# GaggiaBoard_V2.net
KiCad netlist of a schematic drawn in EAGLE
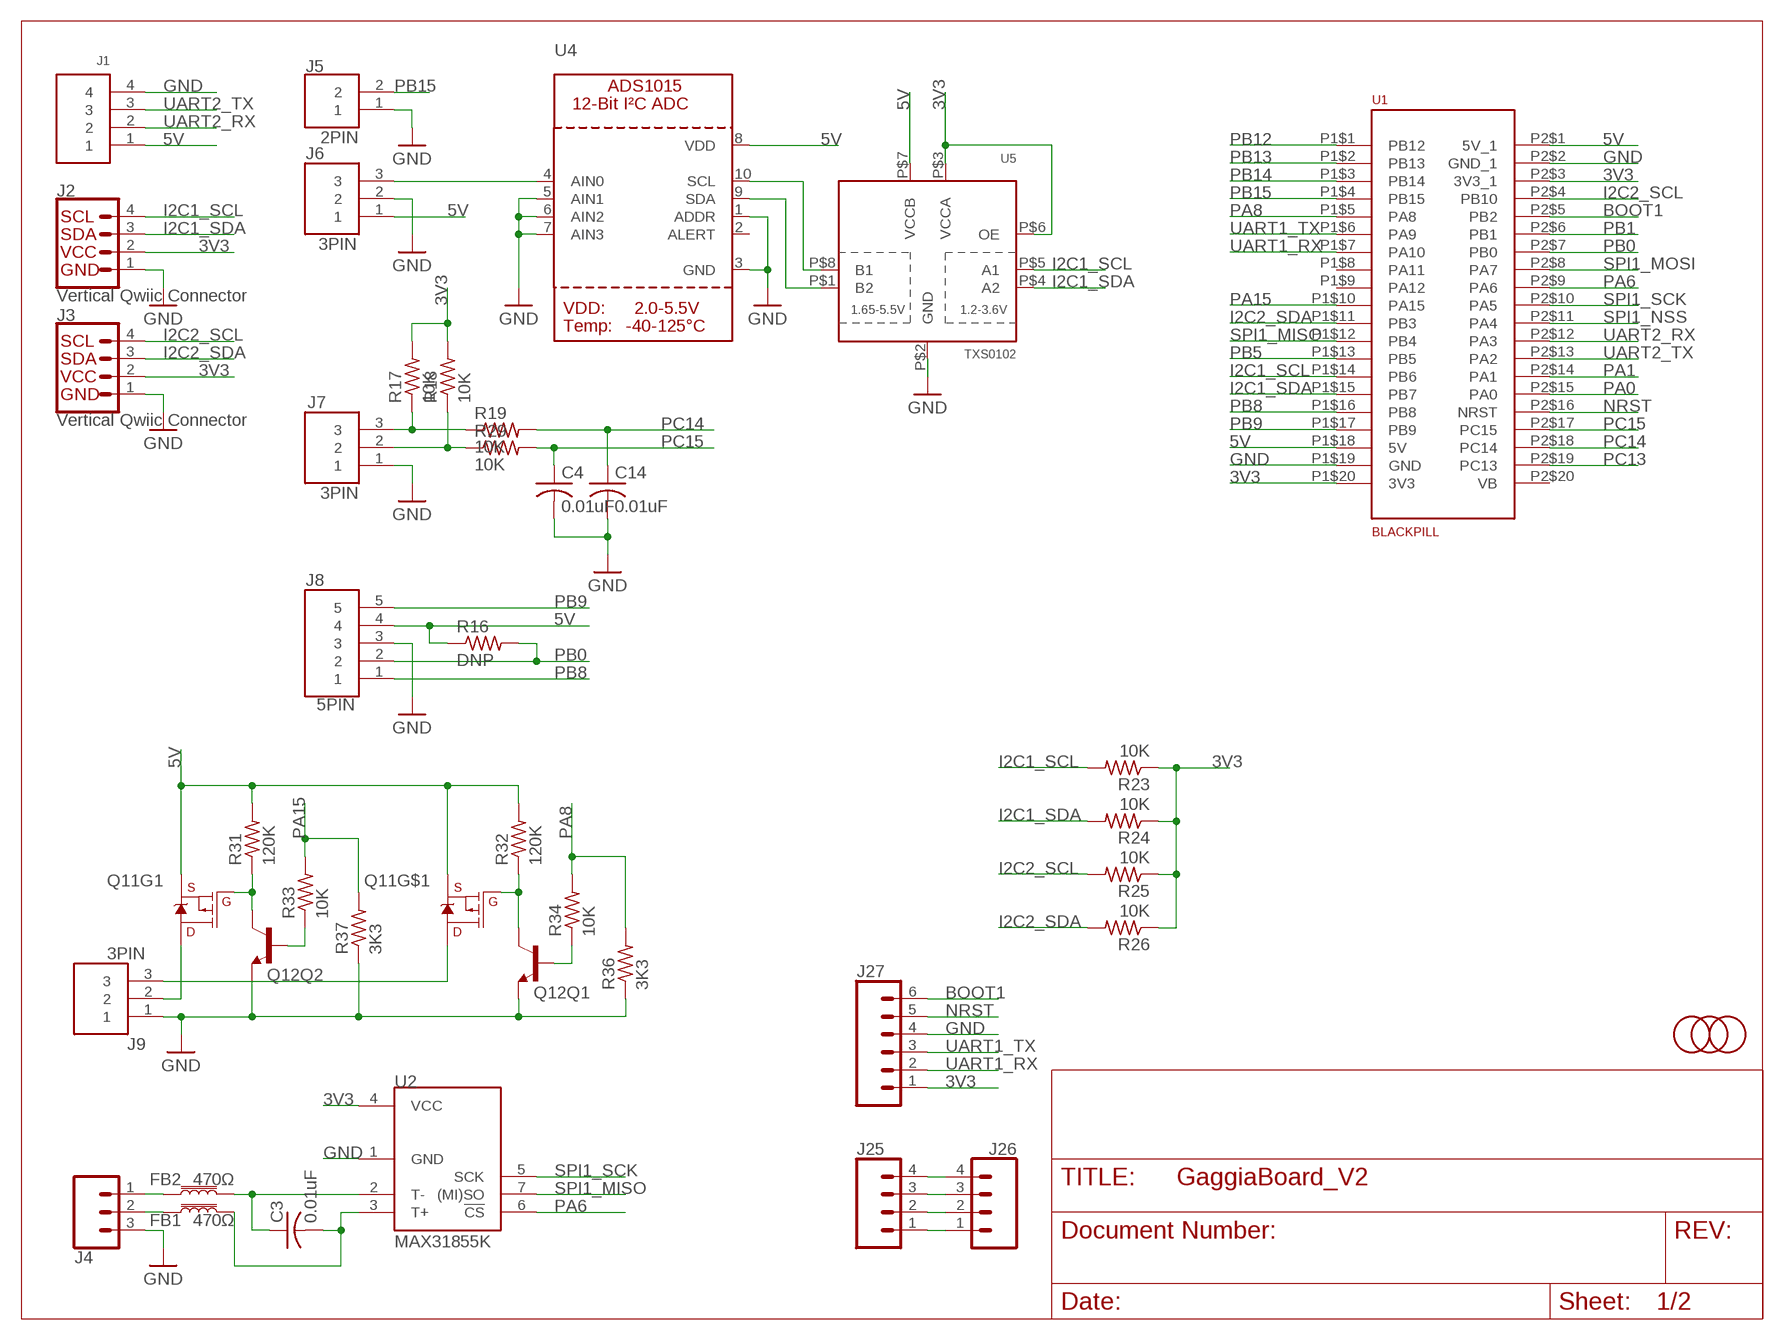
[diagram p0: schematic, sheet 1]
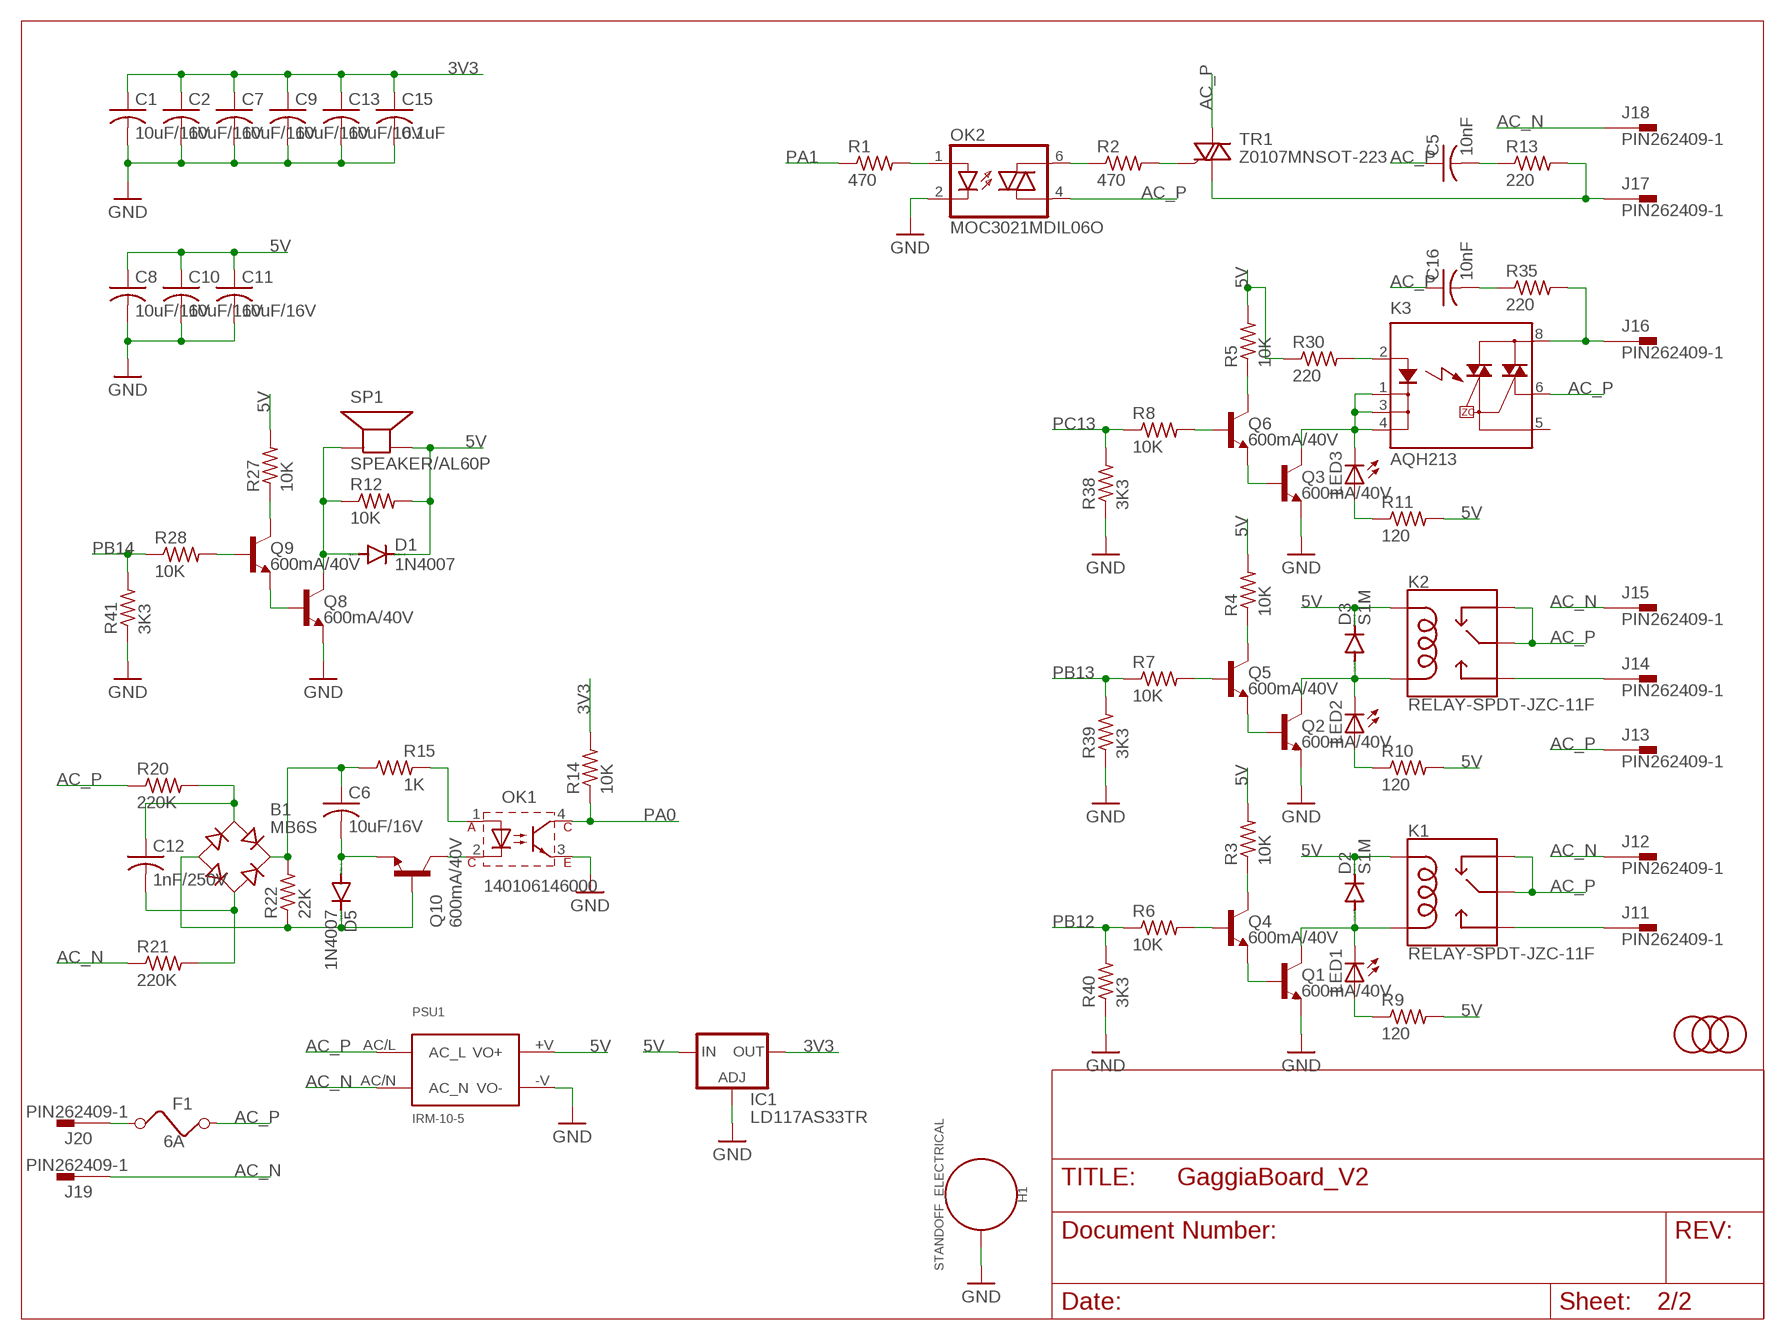
[diagram p1: schematic, sheet 2]

(export (version "E")
  (design (tool "Eeschema 10.0.6"))
  (components
    (comp (ref "C3")
      (value "0.01uF")
      (footprint "eagle-import:C0603")
      (libsource (lib "eagle-import") (part "C-USC0603"))
    )
    (comp (ref "C4")
      (value "0.01uF")
      (footprint "eagle-import:C0603")
      (libsource (lib "eagle-import") (part "C-USC0603"))
    )
    (comp (ref "C14")
      (value "0.01uF")
      (footprint "eagle-import:C0603")
      (libsource (lib "eagle-import") (part "C-USC0603"))
    )
    (comp (ref "FB1")
      (value "470Ω")
      (footprint "eagle-import:0603")
      (libsource (lib "eagle-import") (part "FERRITE_BEAD-0603-470Ω-100MHZ-1A-200MILIΩ"))
    )
    (comp (ref "FB2")
      (value "470Ω")
      (footprint "eagle-import:0603")
      (libsource (lib "eagle-import") (part "FERRITE_BEAD-0603-470Ω-100MHZ-1A-200MILIΩ"))
    )
    (comp (ref "J1")
      (value "4PIN")
      (footprint "eagle-import:B4B-XH-K-S")
      (libsource (lib "eagle-import") (part "4PIN"))
    )
    (comp (ref "J2")
      (value "Vertical Qwiic Connector")
      (footprint "eagle-import:JST04_1MM_VERT")
      (libsource (lib "eagle-import") (part "QWIIC_CONNECTOR"))
    )
    (comp (ref "J3")
      (value "Vertical Qwiic Connector")
      (footprint "eagle-import:JST04_1MM_VERT")
      (libsource (lib "eagle-import") (part "QWIIC_CONNECTOR"))
    )
    (comp (ref "J4")
      (value "CONN_03SCREW")
      (footprint "eagle-import:SCREWTERMINAL-3.5MM-3")
      (libsource (lib "eagle-import") (part "CONN_03SCREW"))
    )
    (comp (ref "J5")
      (value "2PIN")
      (footprint "eagle-import:B2B-PH-K-S")
      (libsource (lib "eagle-import") (part "2PIN"))
    )
    (comp (ref "J6")
      (value "3PIN")
      (footprint "eagle-import:B3B-PH-K-S")
      (libsource (lib "eagle-import") (part "3PIN"))
    )
    (comp (ref "J7")
      (value "3PIN")
      (footprint "eagle-import:B3B-PH-K-S")
      (libsource (lib "eagle-import") (part "3PIN"))
    )
    (comp (ref "J8")
      (value "5PIN")
      (footprint "eagle-import:B5B-PH-K-S")
      (libsource (lib "eagle-import") (part "5PIN"))
    )
    (comp (ref "J9")
      (value "3PIN")
      (footprint "eagle-import:B3B-PH-K-S")
      (libsource (lib "eagle-import") (part "3PIN"))
    )
    (comp (ref "J25")
      (value "CONN_041X04_NO_SILK")
      (footprint "eagle-import:1X04_NO_SILK")
      (libsource (lib "eagle-import") (part "CONN_041X04_NO_SILK"))
    )
    (comp (ref "J26")
      (value "CONN_041X04_NO_SILK")
      (footprint "eagle-import:1X04_NO_SILK")
      (libsource (lib "eagle-import") (part "CONN_041X04_NO_SILK"))
    )
    (comp (ref "J27")
      (value "CONN_06NO_SILK_FEMALE_PTH")
      (footprint "eagle-import:1X06_NO_SILK")
      (libsource (lib "eagle-import") (part "CONN_06NO_SILK_FEMALE_PTH"))
    )
    (comp (ref "MARK1")
      (value "FIDUCIAL")
      (footprint "eagle-import:FIDUCIAL_1MM")
      (libsource (lib "eagle-import") (part "FIDUCIAL"))
    )
    (comp (ref "MARK2")
      (value "FIDUCIAL")
      (footprint "eagle-import:FIDUCIAL_1MM")
      (libsource (lib "eagle-import") (part "FIDUCIAL"))
    )
    (comp (ref "MARK5")
      (value "FIDUCIAL")
      (footprint "eagle-import:FIDUCIAL_1MM")
      (libsource (lib "eagle-import") (part "FIDUCIAL"))
    )
    (comp (ref "Q11")
      (value "MOSFET_PCH_DUAL-DMP2240UDM")
      (footprint "eagle-import:SOT26")
      (fields (field (name "LCSC") "C397948"))
      (libsource (lib "eagle-import") (part "MOSFET_PCH_DUAL-DMP2240UDM"))
    )
    (comp (ref "Q12")
      (value "TRANS_NPN_DUAL-MBT3904DW1T1")
      (footprint "eagle-import:SC70-6")
      (fields (field (name "LCSC") "C896759"))
      (libsource (lib "eagle-import") (part "TRANS_NPN_DUAL-MBT3904DW1T1"))
    )
    (comp (ref "R16")
      (value "DNP")
      (footprint "eagle-import:R0603")
      (libsource (lib "eagle-import") (part "R-US_R0603"))
    )
    (comp (ref "R17")
      (value "10K")
      (footprint "eagle-import:R0603")
      (libsource (lib "eagle-import") (part "R-US_R0603"))
    )
    (comp (ref "R18")
      (value "10K")
      (footprint "eagle-import:R0603")
      (libsource (lib "eagle-import") (part "R-US_R0603"))
    )
    (comp (ref "R19")
      (value "10K")
      (footprint "eagle-import:R0603")
      (libsource (lib "eagle-import") (part "R-US_R0603"))
    )
    (comp (ref "R23")
      (value "10K")
      (footprint "eagle-import:R0603")
      (libsource (lib "eagle-import") (part "R-US_R0603"))
    )
    (comp (ref "R24")
      (value "10K")
      (footprint "eagle-import:R0603")
      (libsource (lib "eagle-import") (part "R-US_R0603"))
    )
    (comp (ref "R25")
      (value "10K")
      (footprint "eagle-import:R0603")
      (libsource (lib "eagle-import") (part "R-US_R0603"))
    )
    (comp (ref "R26")
      (value "10K")
      (footprint "eagle-import:R0603")
      (libsource (lib "eagle-import") (part "R-US_R0603"))
    )
    (comp (ref "R29")
      (value "10K")
      (footprint "eagle-import:R0603")
      (libsource (lib "eagle-import") (part "R-US_R0603"))
    )
    (comp (ref "R31")
      (value "120K")
      (footprint "eagle-import:R0603")
      (libsource (lib "eagle-import") (part "R-US_R0603"))
    )
    (comp (ref "R32")
      (value "120K")
      (footprint "eagle-import:R0603")
      (libsource (lib "eagle-import") (part "R-US_R0603"))
    )
    (comp (ref "R33")
      (value "10K")
      (footprint "eagle-import:R0603")
      (libsource (lib "eagle-import") (part "R-US_R0603"))
    )
    (comp (ref "R34")
      (value "10K")
      (footprint "eagle-import:R0603")
      (libsource (lib "eagle-import") (part "R-US_R0603"))
    )
    (comp (ref "R36")
      (value "3K3")
      (footprint "eagle-import:R0603")
      (libsource (lib "eagle-import") (part "R-US_R0603"))
    )
    (comp (ref "R37")
      (value "3K3")
      (footprint "eagle-import:R0603")
      (libsource (lib "eagle-import") (part "R-US_R0603"))
    )
    (comp (ref "U1")
      (value "BLACKPILL")
      (footprint "eagle-import:BLACKPILL")
      (libsource (lib "eagle-import") (part "BLACKPILL"))
    )
    (comp (ref "U2")
      (value "MAX31855K")
      (footprint "eagle-import:SO08")
      (libsource (lib "eagle-import") (part "MAX31855K"))
    )
    (comp (ref "U4")
      (value "ADC_ADS1015")
      (footprint "eagle-import:MSOP10")
      (libsource (lib "eagle-import") (part "ADC_ADS1015"))
    )
    (comp (ref "U5")
      (value "TXS0102")
      (footprint "eagle-import:VFSOP-8")
      (libsource (lib "eagle-import") (part "TXS0102"))
    )
    (comp (ref "B1")
      (value "MB6S")
      (footprint "eagle-import:SOIC-4")
      (libsource (lib "eagle-import") (part "MBS6"))
    )
    (comp (ref "C1")
      (value "10uF/16V")
      (footprint "eagle-import:C0603")
      (libsource (lib "eagle-import") (part "C-USC0603"))
    )
    (comp (ref "C2")
      (value "10uF/16V")
      (footprint "eagle-import:C0603")
      (libsource (lib "eagle-import") (part "C-USC0603"))
    )
    (comp (ref "C5")
      (value "10nF")
      (footprint "eagle-import:C1206")
      (libsource (lib "eagle-import") (part "C-USC1206"))
    )
    (comp (ref "C6")
      (value "10uF/16V")
      (footprint "eagle-import:C0603")
      (libsource (lib "eagle-import") (part "C-USC0603"))
    )
    (comp (ref "C7")
      (value "10uF/16V")
      (footprint "eagle-import:C0603")
      (libsource (lib "eagle-import") (part "C-USC0603"))
    )
    (comp (ref "C8")
      (value "10uF/16V")
      (footprint "eagle-import:C0603")
      (libsource (lib "eagle-import") (part "C-USC0603"))
    )
    (comp (ref "C9")
      (value "10uF/16V")
      (footprint "eagle-import:C0603")
      (libsource (lib "eagle-import") (part "C-USC0603"))
    )
    (comp (ref "C10")
      (value "10uF/16V")
      (footprint "eagle-import:C0603")
      (libsource (lib "eagle-import") (part "C-USC0603"))
    )
    (comp (ref "C11")
      (value "10uF/16V")
      (footprint "eagle-import:C0603")
      (libsource (lib "eagle-import") (part "C-USC0603"))
    )
    (comp (ref "C12")
      (value "1nF/250V")
      (footprint "eagle-import:C0603")
      (libsource (lib "eagle-import") (part "C-USC0603"))
    )
    (comp (ref "C13")
      (value "10uF/16V")
      (footprint "eagle-import:C0603")
      (libsource (lib "eagle-import") (part "C-USC0603"))
    )
    (comp (ref "C15")
      (value "0.1uF")
      (footprint "eagle-import:C0603")
      (libsource (lib "eagle-import") (part "C-USC0603"))
    )
    (comp (ref "C16")
      (value "10nF")
      (footprint "eagle-import:C1206")
      (libsource (lib "eagle-import") (part "C-USC1206"))
    )
    (comp (ref "D1")
      (value "1N4007")
      (footprint "eagle-import:DO214AC")
      (libsource (lib "eagle-import") (part "DIODE-DO214AC"))
    )
    (comp (ref "D2")
      (value "S1M")
      (footprint "eagle-import:SMA")
      (libsource (lib "eagle-import") (part "S1M"))
    )
    (comp (ref "D3")
      (value "S1M")
      (footprint "eagle-import:SMA")
      (libsource (lib "eagle-import") (part "S1M"))
    )
    (comp (ref "D5")
      (value "1N4007")
      (footprint "eagle-import:DO214AC")
      (libsource (lib "eagle-import") (part "DIODE-DO214AC"))
    )
    (comp (ref "F1")
      (value "6A")
      (footprint "eagle-import:FUSE")
      (libsource (lib "eagle-import") (part "FUSE"))
    )
    (comp (ref "H1")
      (value "STANDOFF_ELECTRICAL")
      (footprint "eagle-import:STANDOFF-ELECTRICAL")
      (libsource (lib "eagle-import") (part "STANDOFF_ELECTRICAL"))
    )
    (comp (ref "IC1")
      (value "LD117AS33TR")
      (footprint "eagle-import:SOT223")
      (libsource (lib "eagle-import") (part "LD117A?S33TR"))
    )
    (comp (ref "J11")
      (value "PIN262409-1")
      (footprint "eagle-import:62409-1")
      (libsource (lib "eagle-import") (part "PIN262409-1"))
    )
    (comp (ref "J12")
      (value "PIN262409-1")
      (footprint "eagle-import:62409-1")
      (libsource (lib "eagle-import") (part "PIN262409-1"))
    )
    (comp (ref "J13")
      (value "PIN262409-1")
      (footprint "eagle-import:62409-1")
      (libsource (lib "eagle-import") (part "PIN262409-1"))
    )
    (comp (ref "J14")
      (value "PIN262409-1")
      (footprint "eagle-import:62409-1")
      (libsource (lib "eagle-import") (part "PIN262409-1"))
    )
    (comp (ref "J15")
      (value "PIN262409-1")
      (footprint "eagle-import:62409-1")
      (libsource (lib "eagle-import") (part "PIN262409-1"))
    )
    (comp (ref "J16")
      (value "PIN262409-1")
      (footprint "eagle-import:62409-1")
      (libsource (lib "eagle-import") (part "PIN262409-1"))
    )
    (comp (ref "J17")
      (value "PIN262409-1")
      (footprint "eagle-import:62409-1")
      (libsource (lib "eagle-import") (part "PIN262409-1"))
    )
    (comp (ref "J18")
      (value "PIN262409-1")
      (footprint "eagle-import:62409-1")
      (libsource (lib "eagle-import") (part "PIN262409-1"))
    )
    (comp (ref "J19")
      (value "PIN262409-1")
      (footprint "eagle-import:62409-1")
      (libsource (lib "eagle-import") (part "PIN262409-1"))
    )
    (comp (ref "J20")
      (value "PIN262409-1")
      (footprint "eagle-import:62409-1")
      (libsource (lib "eagle-import") (part "PIN262409-1"))
    )
    (comp (ref "K1")
      (value "RELAY-SPDT-JZC-11F")
      (footprint "eagle-import:RELAY-JZC")
      (libsource (lib "eagle-import") (part "RELAY-SPDT-JZC-11F"))
    )
    (comp (ref "K2")
      (value "RELAY-SPDT-JZC-11F")
      (footprint "eagle-import:RELAY-JZC")
      (libsource (lib "eagle-import") (part "RELAY-SPDT-JZC-11F"))
    )
    (comp (ref "K3")
      (value "AQH213")
      (footprint "eagle-import:DIL07")
      (libsource (lib "eagle-import") (part "AQH213"))
    )
    (comp (ref "LED1")
      (value "LEDCHIPLED_1206")
      (footprint "eagle-import:CHIPLED_1206")
      (libsource (lib "eagle-import") (part "LEDCHIPLED_1206"))
    )
    (comp (ref "LED2")
      (value "LEDCHIPLED_1206")
      (footprint "eagle-import:CHIPLED_1206")
      (libsource (lib "eagle-import") (part "LEDCHIPLED_1206"))
    )
    (comp (ref "LED3")
      (value "LEDCHIPLED_1206")
      (footprint "eagle-import:CHIPLED_1206")
      (libsource (lib "eagle-import") (part "LEDCHIPLED_1206"))
    )
    (comp (ref "MARK3")
      (value "FIDUCIAL")
      (footprint "eagle-import:FIDUCIAL_1MM")
      (libsource (lib "eagle-import") (part "FIDUCIAL"))
    )
    (comp (ref "MARK4")
      (value "FIDUCIAL")
      (footprint "eagle-import:FIDUCIAL_1MM")
      (libsource (lib "eagle-import") (part "FIDUCIAL"))
    )
    (comp (ref "MARK6")
      (value "FIDUCIAL")
      (footprint "eagle-import:FIDUCIAL_1MM")
      (libsource (lib "eagle-import") (part "FIDUCIAL"))
    )
    (comp (ref "OK1")
      (value "140106146000")
      (footprint "eagle-import:WL-OCPT_LSOP4")
      (libsource (lib "eagle-import") (part "WL-OCPT_SERIES_101X_140106146000"))
    )
    (comp (ref "OK2")
      (value "MOC3021MDIL06O")
      (footprint "eagle-import:DIL06O")
      (libsource (lib "eagle-import") (part "MOC3021MDIL06O"))
    )
    (comp (ref "PSU1")
      (value "IRM-10-5")
      (footprint "eagle-import:IRM-10")
      (fields (field (name "SPICEPREFIX") "E"))
      (libsource (lib "eagle-import") (part "IRM-10-5"))
    )
    (comp (ref "Q1")
      (value "600mA/40V")
      (footprint "eagle-import:SOT23-3")
      (libsource (lib "eagle-import") (part "TRANS_NPN-MMBT2222AL"))
    )
    (comp (ref "Q2")
      (value "600mA/40V")
      (footprint "eagle-import:SOT23-3")
      (libsource (lib "eagle-import") (part "TRANS_NPN-MMBT2222AL"))
    )
    (comp (ref "Q3")
      (value "600mA/40V")
      (footprint "eagle-import:SOT23-3")
      (libsource (lib "eagle-import") (part "TRANS_NPN-MMBT2222AL"))
    )
    (comp (ref "Q4")
      (value "600mA/40V")
      (footprint "eagle-import:SOT23-3")
      (libsource (lib "eagle-import") (part "TRANS_NPN-MMBT2222AL"))
    )
    (comp (ref "Q5")
      (value "600mA/40V")
      (footprint "eagle-import:SOT23-3")
      (libsource (lib "eagle-import") (part "TRANS_NPN-MMBT2222AL"))
    )
    (comp (ref "Q6")
      (value "600mA/40V")
      (footprint "eagle-import:SOT23-3")
      (libsource (lib "eagle-import") (part "TRANS_NPN-MMBT2222AL"))
    )
    (comp (ref "Q8")
      (value "600mA/40V")
      (footprint "eagle-import:SOT23-3")
      (libsource (lib "eagle-import") (part "TRANS_NPN-MMBT2222AL"))
    )
    (comp (ref "Q9")
      (value "600mA/40V")
      (footprint "eagle-import:SOT23-3")
      (libsource (lib "eagle-import") (part "TRANS_NPN-MMBT2222AL"))
    )
    (comp (ref "Q10")
      (value "600mA/40V")
      (footprint "eagle-import:SOT23-3")
      (libsource (lib "eagle-import") (part "TRANS_NPN-MMBT2222AL"))
    )
    (comp (ref "R1")
      (value "470")
      (footprint "eagle-import:R0603")
      (libsource (lib "eagle-import") (part "R-US_R0603"))
    )
    (comp (ref "R2")
      (value "470")
      (footprint "eagle-import:R0603")
      (libsource (lib "eagle-import") (part "R-US_R0603"))
    )
    (comp (ref "R3")
      (value "10K")
      (footprint "eagle-import:R0603")
      (libsource (lib "eagle-import") (part "R-US_R0603"))
    )
    (comp (ref "R4")
      (value "10K")
      (footprint "eagle-import:R0603")
      (libsource (lib "eagle-import") (part "R-US_R0603"))
    )
    (comp (ref "R5")
      (value "10K")
      (footprint "eagle-import:R0603")
      (libsource (lib "eagle-import") (part "R-US_R0603"))
    )
    (comp (ref "R6")
      (value "10K")
      (footprint "eagle-import:R0603")
      (libsource (lib "eagle-import") (part "R-US_R0603"))
    )
    (comp (ref "R7")
      (value "10K")
      (footprint "eagle-import:R0603")
      (libsource (lib "eagle-import") (part "R-US_R0603"))
    )
    (comp (ref "R8")
      (value "10K")
      (footprint "eagle-import:R0603")
      (libsource (lib "eagle-import") (part "R-US_R0603"))
    )
    (comp (ref "R9")
      (value "120")
      (footprint "eagle-import:R0603")
      (libsource (lib "eagle-import") (part "R-US_R0603"))
    )
    (comp (ref "R10")
      (value "120")
      (footprint "eagle-import:R0603")
      (libsource (lib "eagle-import") (part "R-US_R0603"))
    )
    (comp (ref "R11")
      (value "120")
      (footprint "eagle-import:R0603")
      (libsource (lib "eagle-import") (part "R-US_R0603"))
    )
    (comp (ref "R12")
      (value "10K")
      (footprint "eagle-import:R0603")
      (libsource (lib "eagle-import") (part "R-US_R0603"))
    )
    (comp (ref "R13")
      (value "220")
      (footprint "eagle-import:R2512")
      (libsource (lib "eagle-import") (part "R-US_R2512"))
    )
    (comp (ref "R14")
      (value "10K")
      (footprint "eagle-import:R0603")
      (libsource (lib "eagle-import") (part "R-US_R0603"))
    )
    (comp (ref "R15")
      (value "1K")
      (footprint "eagle-import:R0603")
      (libsource (lib "eagle-import") (part "R-US_R0603"))
    )
    (comp (ref "R20")
      (value "220K")
      (footprint "eagle-import:R1206")
      (libsource (lib "eagle-import") (part "R-US_R1206"))
    )
    (comp (ref "R21")
      (value "220K")
      (footprint "eagle-import:R1206")
      (libsource (lib "eagle-import") (part "R-US_R1206"))
    )
    (comp (ref "R22")
      (value "22K")
      (footprint "eagle-import:R0603")
      (libsource (lib "eagle-import") (part "R-US_R0603"))
    )
    (comp (ref "R27")
      (value "10K")
      (footprint "eagle-import:R0603")
      (libsource (lib "eagle-import") (part "R-US_R0603"))
    )
    (comp (ref "R28")
      (value "10K")
      (footprint "eagle-import:R0603")
      (libsource (lib "eagle-import") (part "R-US_R0603"))
    )
    (comp (ref "R30")
      (value "220")
      (footprint "eagle-import:R0603")
      (libsource (lib "eagle-import") (part "R-US_R0603"))
    )
    (comp (ref "R35")
      (value "220")
      (footprint "eagle-import:R2512")
      (libsource (lib "eagle-import") (part "R-US_R2512"))
    )
    (comp (ref "R38")
      (value "3K3")
      (footprint "eagle-import:R0603")
      (libsource (lib "eagle-import") (part "R-US_R0603"))
    )
    (comp (ref "R39")
      (value "3K3")
      (footprint "eagle-import:R0603")
      (libsource (lib "eagle-import") (part "R-US_R0603"))
    )
    (comp (ref "R40")
      (value "3K3")
      (footprint "eagle-import:R0603")
      (libsource (lib "eagle-import") (part "R-US_R0603"))
    )
    (comp (ref "R41")
      (value "3K3")
      (footprint "eagle-import:R0603")
      (libsource (lib "eagle-import") (part "R-US_R0603"))
    )
    (comp (ref "SP1")
      (value "SPEAKER/AL60P")
      (footprint "eagle-import:AL60P")
      (libsource (lib "eagle-import") (part "SPEAKER/AL60P"))
    )
    (comp (ref "TR1")
      (value "Z0107MNSOT-223")
      (footprint "eagle-import:SOT223")
      (libsource (lib "eagle-import") (part "Z0107MNSOT-223"))
    )
  )
  (nets
    (net (code "1") (name "3V3") (class "Default")
      (node (ref "C1") (pin "1") (pinfunction "1_1") (pintype "passive"))
      (node (ref "C13") (pin "1") (pinfunction "1_1") (pintype "passive"))
      (node (ref "C15") (pin "1") (pinfunction "1_1") (pintype "passive"))
      (node (ref "C2") (pin "1") (pinfunction "1_1") (pintype "passive"))
      (node (ref "C7") (pin "1") (pinfunction "1_1") (pintype "passive"))
      (node (ref "C9") (pin "1") (pinfunction "1_1") (pintype "passive"))
      (node (ref "IC1") (pin "4") (pinfunction "OUT_4") (pintype "passive"))
      (node (ref "J2") (pin "2") (pinfunction "2_2") (pintype "power_in"))
      (node (ref "J25") (pin "1") (pinfunction "1_1") (pintype "passive"))
      (node (ref "J26") (pin "1") (pinfunction "1_1") (pintype "passive"))
      (node (ref "J27") (pin "1") (pinfunction "1_1") (pintype "passive"))
      (node (ref "J3") (pin "2") (pinfunction "2_2") (pintype "power_in"))
      (node (ref "R14") (pin "2") (pinfunction "2_2") (pintype "passive"))
      (node (ref "R17") (pin "2") (pinfunction "2_2") (pintype "passive"))
      (node (ref "R18") (pin "2") (pinfunction "2_2") (pintype "passive"))
      (node (ref "R23") (pin "1") (pinfunction "1_1") (pintype "passive"))
      (node (ref "R24") (pin "1") (pinfunction "1_1") (pintype "passive"))
      (node (ref "R25") (pin "1") (pinfunction "1_1") (pintype "passive"))
      (node (ref "R26") (pin "1") (pinfunction "1_1") (pintype "passive"))
      (node (ref "U1") (pin "P1$20") (pinfunction "3V3_P1$20") (pintype "power_in"))
      (node (ref "U1") (pin "P2$3") (pinfunction "3V3_1_P2$3") (pintype "power_in"))
      (node (ref "U2") (pin "4") (pinfunction "VCC_4") (pintype "bidirectional"))
      (node (ref "U5") (pin "P$3") (pinfunction "VCCA_P$3") (pintype "bidirectional"))
      (node (ref "U5") (pin "P$6") (pinfunction "OE_P$6") (pintype "bidirectional"))
    )
    (net (code "2") (name "5V") (class "Default")
      (node (ref "C10") (pin "1") (pinfunction "1_1") (pintype "passive"))
      (node (ref "C11") (pin "1") (pinfunction "1_1") (pintype "passive"))
      (node (ref "C8") (pin "1") (pinfunction "1_1") (pintype "passive"))
      (node (ref "D1") (pin "C") (pinfunction "C_C") (pintype "passive"))
      (node (ref "D2") (pin "C") (pinfunction "C_C") (pintype "passive"))
      (node (ref "D3") (pin "C") (pinfunction "C_C") (pintype "passive"))
      (node (ref "IC1") (pin "3") (pinfunction "IN_3") (pintype "input"))
      (node (ref "J1") (pin "1") (pinfunction "1_1") (pintype "bidirectional"))
      (node (ref "J6") (pin "1") (pinfunction "1_1") (pintype "bidirectional"))
      (node (ref "J8") (pin "4") (pinfunction "4_4") (pintype "bidirectional"))
      (node (ref "K1") (pin "5") (pinfunction "COIL1_5") (pintype "bidirectional"))
      (node (ref "K2") (pin "5") (pinfunction "COIL1_5") (pintype "bidirectional"))
      (node (ref "PSU1") (pin "+V") (pinfunction "VO+_+V") (pintype "bidirectional"))
      (node (ref "Q11") (pin "S1") (pinfunction "S_S1") (pintype "bidirectional"))
      (node (ref "Q11") (pin "S2") (pinfunction "S_S2") (pintype "bidirectional"))
      (node (ref "R10") (pin "2") (pinfunction "2_2") (pintype "passive"))
      (node (ref "R11") (pin "2") (pinfunction "2_2") (pintype "passive"))
      (node (ref "R12") (pin "2") (pinfunction "2_2") (pintype "passive"))
      (node (ref "R16") (pin "1") (pinfunction "1_1") (pintype "passive"))
      (node (ref "R27") (pin "2") (pinfunction "2_2") (pintype "passive"))
      (node (ref "R3") (pin "2") (pinfunction "2_2") (pintype "passive"))
      (node (ref "R30") (pin "1") (pinfunction "1_1") (pintype "passive"))
      (node (ref "R31") (pin "2") (pinfunction "2_2") (pintype "passive"))
      (node (ref "R32") (pin "2") (pinfunction "2_2") (pintype "passive"))
      (node (ref "R4") (pin "2") (pinfunction "2_2") (pintype "passive"))
      (node (ref "R5") (pin "2") (pinfunction "2_2") (pintype "passive"))
      (node (ref "R9") (pin "2") (pinfunction "2_2") (pintype "passive"))
      (node (ref "SP1") (pin "2") (pinfunction "-_2") (pintype "passive"))
      (node (ref "U1") (pin "P1$18") (pinfunction "5V_P1$18") (pintype "power_in"))
      (node (ref "U1") (pin "P2$1") (pinfunction "5V_1_P2$1") (pintype "power_in"))
      (node (ref "U4") (pin "8") (pinfunction "VDD_8") (pintype "bidirectional"))
      (node (ref "U5") (pin "P$7") (pinfunction "VCCB_P$7") (pintype "bidirectional"))
    )
    (net (code "3") (name "AC_N") (class "Default")
      (node (ref "J12") (pin "A1") (pinfunction "1_A1") (pintype "passive"))
      (node (ref "J12") (pin "A2") (pinfunction "1_A2") (pintype "passive"))
      (node (ref "J15") (pin "A1") (pinfunction "1_A1") (pintype "passive"))
      (node (ref "J15") (pin "A2") (pinfunction "1_A2") (pintype "passive"))
      (node (ref "J18") (pin "A1") (pinfunction "1_A1") (pintype "passive"))
      (node (ref "J18") (pin "A2") (pinfunction "1_A2") (pintype "passive"))
      (node (ref "J19") (pin "A1") (pinfunction "1_A1") (pintype "passive"))
      (node (ref "J19") (pin "A2") (pinfunction "1_A2") (pintype "passive"))
      (node (ref "PSU1") (pin "AC/N") (pinfunction "AC_N_AC/N") (pintype "bidirectional"))
      (node (ref "R21") (pin "1") (pinfunction "1_1") (pintype "passive"))
    )
    (net (code "4") (name "AC_P") (class "Default")
      (node (ref "C16") (pin "1") (pinfunction "1_1") (pintype "passive"))
      (node (ref "C5") (pin "1") (pinfunction "1_1") (pintype "passive"))
      (node (ref "F1") (pin "2") (pinfunction "2_2") (pintype "passive"))
      (node (ref "J13") (pin "A1") (pinfunction "1_A1") (pintype "passive"))
      (node (ref "J13") (pin "A2") (pinfunction "1_A2") (pintype "passive"))
      (node (ref "K1") (pin "2") (pinfunction "NC_2") (pintype "bidirectional"))
      (node (ref "K1") (pin "4") (pinfunction "MAIN_4") (pintype "bidirectional"))
      (node (ref "K2") (pin "2") (pinfunction "NC_2") (pintype "bidirectional"))
      (node (ref "K2") (pin "4") (pinfunction "MAIN_4") (pintype "bidirectional"))
      (node (ref "K3") (pin "6") (pinfunction "DS3_6") (pintype "passive"))
      (node (ref "OK2") (pin "4") (pinfunction "A1_4") (pintype "passive"))
      (node (ref "PSU1") (pin "AC/L") (pinfunction "AC_L_AC/L") (pintype "bidirectional"))
      (node (ref "R20") (pin "1") (pinfunction "1_1") (pintype "passive"))
      (node (ref "TR1") (pin "2") (pinfunction "A2_2") (pintype "passive"))
      (node (ref "TR1") (pin "4") (pinfunction "A2_4") (pintype "passive"))
    )
    (net (code "5") (name "BOOT1") (class "Default")
      (node (ref "J27") (pin "6") (pinfunction "6_6") (pintype "passive"))
      (node (ref "U1") (pin "P2$5") (pinfunction "PB2_P2$5") (pintype "bidirectional"))
    )
    (net (code "6") (name "GND") (class "Default")
      (node (ref "C1") (pin "2") (pinfunction "2_2") (pintype "passive"))
      (node (ref "C10") (pin "2") (pinfunction "2_2") (pintype "passive"))
      (node (ref "C11") (pin "2") (pinfunction "2_2") (pintype "passive"))
      (node (ref "C13") (pin "2") (pinfunction "2_2") (pintype "passive"))
      (node (ref "C14") (pin "2") (pinfunction "2_2") (pintype "passive"))
      (node (ref "C15") (pin "2") (pinfunction "2_2") (pintype "passive"))
      (node (ref "C2") (pin "2") (pinfunction "2_2") (pintype "passive"))
      (node (ref "C4") (pin "2") (pinfunction "2_2") (pintype "passive"))
      (node (ref "C7") (pin "2") (pinfunction "2_2") (pintype "passive"))
      (node (ref "C8") (pin "2") (pinfunction "2_2") (pintype "passive"))
      (node (ref "C9") (pin "2") (pinfunction "2_2") (pintype "passive"))
      (node (ref "H1") (pin "P1") (pinfunction "P$1_P1") (pintype "bidirectional"))
      (node (ref "IC1") (pin "1") (pinfunction "ADJ_1") (pintype "input"))
      (node (ref "J1") (pin "4") (pinfunction "4_4") (pintype "bidirectional"))
      (node (ref "J2") (pin "1") (pinfunction "1_1") (pintype "power_in"))
      (node (ref "J25") (pin "4") (pinfunction "4_4") (pintype "passive"))
      (node (ref "J26") (pin "4") (pinfunction "4_4") (pintype "passive"))
      (node (ref "J27") (pin "4") (pinfunction "4_4") (pintype "passive"))
      (node (ref "J3") (pin "1") (pinfunction "1_1") (pintype "power_in"))
      (node (ref "J4") (pin "3") (pinfunction "3_3") (pintype "passive"))
      (node (ref "J5") (pin "1") (pinfunction "1_1") (pintype "bidirectional"))
      (node (ref "J6") (pin "2") (pinfunction "2_2") (pintype "bidirectional"))
      (node (ref "J7") (pin "1") (pinfunction "1_1") (pintype "bidirectional"))
      (node (ref "J8") (pin "3") (pinfunction "3_3") (pintype "bidirectional"))
      (node (ref "J9") (pin "1") (pinfunction "1_1") (pintype "bidirectional"))
      (node (ref "OK1") (pin "3") (pinfunction "3_3") (pintype "passive"))
      (node (ref "OK2") (pin "2") (pinfunction "C_2") (pintype "passive"))
      (node (ref "PSU1") (pin "-V") (pinfunction "VO-_-V") (pintype "bidirectional"))
      (node (ref "Q1") (pin "2") (pinfunction "E_2") (pintype "passive"))
      (node (ref "Q12") (pin "1") (pinfunction "E_1") (pintype "passive"))
      (node (ref "Q12") (pin "4") (pinfunction "E_4") (pintype "passive"))
      (node (ref "Q2") (pin "2") (pinfunction "E_2") (pintype "passive"))
      (node (ref "Q3") (pin "2") (pinfunction "E_2") (pintype "passive"))
      (node (ref "Q8") (pin "2") (pinfunction "E_2") (pintype "passive"))
      (node (ref "R36") (pin "1") (pinfunction "1_1") (pintype "passive"))
      (node (ref "R37") (pin "1") (pinfunction "1_1") (pintype "passive"))
      (node (ref "R38") (pin "1") (pinfunction "1_1") (pintype "passive"))
      (node (ref "R39") (pin "1") (pinfunction "1_1") (pintype "passive"))
      (node (ref "R40") (pin "1") (pinfunction "1_1") (pintype "passive"))
      (node (ref "R41") (pin "1") (pinfunction "1_1") (pintype "passive"))
      (node (ref "U1") (pin "P1$19") (pinfunction "GND_P1$19") (pintype "power_in"))
      (node (ref "U1") (pin "P2$2") (pinfunction "GND_1_P2$2") (pintype "power_in"))
      (node (ref "U2") (pin "1") (pinfunction "GND_1") (pintype "bidirectional"))
      (node (ref "U4") (pin "1") (pinfunction "ADDR_1") (pintype "bidirectional"))
      (node (ref "U4") (pin "3") (pinfunction "GND_3") (pintype "bidirectional"))
      (node (ref "U4") (pin "5") (pinfunction "AIN1_5") (pintype "bidirectional"))
      (node (ref "U4") (pin "6") (pinfunction "AIN2_6") (pintype "bidirectional"))
      (node (ref "U4") (pin "7") (pinfunction "AIN3_7") (pintype "bidirectional"))
      (node (ref "U5") (pin "P$2") (pinfunction "GND_P$2") (pintype "bidirectional"))
    )
    (net (code "7") (name "I2C1_SCL") (class "Default")
      (node (ref "J2") (pin "4") (pinfunction "4_4") (pintype "passive"))
      (node (ref "R23") (pin "2") (pinfunction "2_2") (pintype "passive"))
      (node (ref "U1") (pin "P1$14") (pinfunction "PB6_P1$14") (pintype "bidirectional"))
      (node (ref "U5") (pin "P$5") (pinfunction "A1_P$5") (pintype "bidirectional"))
    )
    (net (code "8") (name "I2C1_SDA") (class "Default")
      (node (ref "J2") (pin "3") (pinfunction "3_3") (pintype "passive"))
      (node (ref "R24") (pin "2") (pinfunction "2_2") (pintype "passive"))
      (node (ref "U1") (pin "P1$15") (pinfunction "PB7_P1$15") (pintype "bidirectional"))
      (node (ref "U5") (pin "P$4") (pinfunction "A2_P$4") (pintype "bidirectional"))
    )
    (net (code "9") (name "I2C2_SCL") (class "Default")
      (node (ref "J3") (pin "4") (pinfunction "4_4") (pintype "passive"))
      (node (ref "R25") (pin "2") (pinfunction "2_2") (pintype "passive"))
      (node (ref "U1") (pin "P2$4") (pinfunction "PB10_P2$4") (pintype "bidirectional"))
    )
    (net (code "10") (name "I2C2_SDA") (class "Default")
      (node (ref "J3") (pin "3") (pinfunction "3_3") (pintype "passive"))
      (node (ref "R26") (pin "2") (pinfunction "2_2") (pintype "passive"))
      (node (ref "U1") (pin "P1$11") (pinfunction "PB3_P1$11") (pintype "bidirectional"))
    )
    (net (code "11") (name "NRST") (class "Default")
      (node (ref "J27") (pin "5") (pinfunction "5_5") (pintype "passive"))
      (node (ref "U1") (pin "P2$16") (pinfunction "NRST_P2$16") (pintype "bidirectional"))
    )
    (net (code "12") (name "Net-(B1-AC1)") (class "Default")
      (node (ref "B1") (pin "~1") (pinfunction "AC1_~1") (pintype "passive"))
      (node (ref "C12") (pin "2") (pinfunction "2_2") (pintype "passive"))
      (node (ref "R21") (pin "2") (pinfunction "2_2") (pintype "passive"))
    )
    (net (code "13") (name "Net-(B1-AC2)") (class "Default")
      (node (ref "B1") (pin "~2") (pinfunction "AC2_~2") (pintype "passive"))
      (node (ref "C12") (pin "1") (pinfunction "1_1") (pintype "passive"))
      (node (ref "R20") (pin "2") (pinfunction "2_2") (pintype "passive"))
    )
    (net (code "14") (name "Net-(B1-Pad+)") (class "Default")
      (node (ref "B1") (pin "+") (pinfunction "+_+") (pintype "passive"))
      (node (ref "C6") (pin "1") (pinfunction "1_1") (pintype "passive"))
      (node (ref "R15") (pin "1") (pinfunction "1_1") (pintype "passive"))
      (node (ref "R22") (pin "2") (pinfunction "2_2") (pintype "passive"))
    )
    (net (code "15") (name "Net-(C5-Pad2)") (class "Default")
      (node (ref "C5") (pin "2") (pinfunction "2_2") (pintype "passive"))
      (node (ref "R13") (pin "1") (pinfunction "1_1") (pintype "passive"))
    )
    (net (code "16") (name "Net-(C16-Pad2)") (class "Default")
      (node (ref "C16") (pin "2") (pinfunction "2_2") (pintype "passive"))
      (node (ref "R35") (pin "1") (pinfunction "1_1") (pintype "passive"))
    )
    (net (code "17") (name "Net-(F1-Pad1)") (class "Default")
      (node (ref "F1") (pin "1") (pinfunction "1_1") (pintype "passive"))
      (node (ref "J20") (pin "A1") (pinfunction "1_A1") (pintype "passive"))
      (node (ref "J20") (pin "A2") (pinfunction "1_A2") (pintype "passive"))
    )
    (net (code "18") (name "Net-(FB1-Pad1)") (class "Default")
      (node (ref "FB1") (pin "1") (pinfunction "1_1") (pintype "passive"))
      (node (ref "J4") (pin "2") (pinfunction "2_2") (pintype "passive"))
    )
    (net (code "19") (name "Net-(FB2-Pad1)") (class "Default")
      (node (ref "FB2") (pin "1") (pinfunction "1_1") (pintype "passive"))
      (node (ref "J4") (pin "1") (pinfunction "1_1") (pintype "passive"))
    )
    (net (code "20") (name "Net-(J7-Pad2)") (class "Default")
      (node (ref "J7") (pin "2") (pinfunction "2_2") (pintype "bidirectional"))
      (node (ref "R18") (pin "1") (pinfunction "1_1") (pintype "passive"))
      (node (ref "R29") (pin "1") (pinfunction "1_1") (pintype "passive"))
    )
    (net (code "21") (name "Net-(J7-Pad3)") (class "Default")
      (node (ref "J7") (pin "3") (pinfunction "3_3") (pintype "bidirectional"))
      (node (ref "R17") (pin "1") (pinfunction "1_1") (pintype "passive"))
      (node (ref "R19") (pin "1") (pinfunction "1_1") (pintype "passive"))
    )
    (net (code "22") (name "Net-(J25-Pad2)") (class "Default")
      (node (ref "J25") (pin "2") (pinfunction "2_2") (pintype "passive"))
      (node (ref "J26") (pin "2") (pinfunction "2_2") (pintype "passive"))
    )
    (net (code "23") (name "Net-(J25-Pad3)") (class "Default")
      (node (ref "J25") (pin "3") (pinfunction "3_3") (pintype "passive"))
      (node (ref "J26") (pin "3") (pinfunction "3_3") (pintype "passive"))
    )
    (net (code "24") (name "Net-(K1-COIL2)") (class "Default")
      (node (ref "D2") (pin "A") (pinfunction "A_A") (pintype "passive"))
      (node (ref "K1") (pin "1") (pinfunction "COIL2_1") (pintype "bidirectional"))
      (node (ref "LED1") (pin "C") (pinfunction "C_C") (pintype "passive"))
      (node (ref "Q1") (pin "3") (pinfunction "C_3") (pintype "passive"))
    )
    (net (code "25") (name "Net-(K1-NO)") (class "Default")
      (node (ref "J11") (pin "A1") (pinfunction "1_A1") (pintype "passive"))
      (node (ref "J11") (pin "A2") (pinfunction "1_A2") (pintype "passive"))
      (node (ref "K1") (pin "3") (pinfunction "NO_3") (pintype "bidirectional"))
    )
    (net (code "26") (name "Net-(K2-COIL2)") (class "Default")
      (node (ref "D3") (pin "A") (pinfunction "A_A") (pintype "passive"))
      (node (ref "K2") (pin "1") (pinfunction "COIL2_1") (pintype "bidirectional"))
      (node (ref "LED2") (pin "C") (pinfunction "C_C") (pintype "passive"))
      (node (ref "Q2") (pin "3") (pinfunction "C_3") (pintype "passive"))
    )
    (net (code "27") (name "Net-(K2-NO)") (class "Default")
      (node (ref "J14") (pin "A1") (pinfunction "1_A1") (pintype "passive"))
      (node (ref "J14") (pin "A2") (pinfunction "1_A2") (pintype "passive"))
      (node (ref "K2") (pin "3") (pinfunction "NO_3") (pintype "bidirectional"))
    )
    (net (code "28") (name "Net-(K3-A)") (class "Default")
      (node (ref "K3") (pin "2") (pinfunction "A_2") (pintype "passive"))
      (node (ref "R30") (pin "2") (pinfunction "2_2") (pintype "passive"))
    )
    (net (code "29") (name "Net-(K3-DS1)") (class "Default")
      (node (ref "J16") (pin "A1") (pinfunction "1_A1") (pintype "passive"))
      (node (ref "J16") (pin "A2") (pinfunction "1_A2") (pintype "passive"))
      (node (ref "K3") (pin "8") (pinfunction "DS1_8") (pintype "passive"))
      (node (ref "R35") (pin "2") (pinfunction "2_2") (pintype "passive"))
    )
    (net (code "30") (name "Net-(K3-K)") (class "Default")
      (node (ref "K3") (pin "1") (pinfunction "K_1") (pintype "passive"))
      (node (ref "K3") (pin "3") (pinfunction "K1_3") (pintype "passive"))
      (node (ref "K3") (pin "4") (pinfunction "K2_4") (pintype "passive"))
      (node (ref "LED3") (pin "C") (pinfunction "C_C") (pintype "passive"))
      (node (ref "Q3") (pin "3") (pinfunction "C_3") (pintype "passive"))
    )
    (net (code "31") (name "Net-(LED1-PadA)") (class "Default")
      (node (ref "LED1") (pin "A") (pinfunction "A_A") (pintype "passive"))
      (node (ref "R9") (pin "1") (pinfunction "1_1") (pintype "passive"))
    )
    (net (code "32") (name "Net-(LED2-PadA)") (class "Default")
      (node (ref "LED2") (pin "A") (pinfunction "A_A") (pintype "passive"))
      (node (ref "R10") (pin "1") (pinfunction "1_1") (pintype "passive"))
    )
    (net (code "33") (name "Net-(LED3-PadA)") (class "Default")
      (node (ref "LED3") (pin "A") (pinfunction "A_A") (pintype "passive"))
      (node (ref "R11") (pin "1") (pinfunction "1_1") (pintype "passive"))
    )
    (net (code "34") (name "Net-(OK1-Pad1)") (class "Default")
      (node (ref "OK1") (pin "1") (pinfunction "1_1") (pintype "passive"))
      (node (ref "R15") (pin "2") (pinfunction "2_2") (pintype "passive"))
    )
    (net (code "35") (name "Net-(OK2-A)") (class "Default")
      (node (ref "OK2") (pin "1") (pinfunction "A_1") (pintype "passive"))
      (node (ref "R1") (pin "2") (pinfunction "2_2") (pintype "passive"))
    )
    (net (code "36") (name "Net-(OK2-A2)") (class "Default")
      (node (ref "OK2") (pin "6") (pinfunction "A2_6") (pintype "passive"))
      (node (ref "R2") (pin "1") (pinfunction "1_1") (pintype "passive"))
    )
    (net (code "37") (name "Net-(Q1-B)") (class "Default")
      (node (ref "Q1") (pin "1") (pinfunction "B_1") (pintype "passive"))
      (node (ref "Q4") (pin "2") (pinfunction "E_2") (pintype "passive"))
    )
    (net (code "38") (name "Net-(Q2-B)") (class "Default")
      (node (ref "Q2") (pin "1") (pinfunction "B_1") (pintype "passive"))
      (node (ref "Q5") (pin "2") (pinfunction "E_2") (pintype "passive"))
    )
    (net (code "39") (name "Net-(Q3-B)") (class "Default")
      (node (ref "Q3") (pin "1") (pinfunction "B_1") (pintype "passive"))
      (node (ref "Q6") (pin "2") (pinfunction "E_2") (pintype "passive"))
    )
    (net (code "40") (name "Net-(Q4-B)") (class "Default")
      (node (ref "Q4") (pin "1") (pinfunction "B_1") (pintype "passive"))
      (node (ref "R6") (pin "2") (pinfunction "2_2") (pintype "passive"))
    )
    (net (code "41") (name "Net-(Q4-C)") (class "Default")
      (node (ref "Q4") (pin "3") (pinfunction "C_3") (pintype "passive"))
      (node (ref "R3") (pin "1") (pinfunction "1_1") (pintype "passive"))
    )
    (net (code "42") (name "Net-(Q5-B)") (class "Default")
      (node (ref "Q5") (pin "1") (pinfunction "B_1") (pintype "passive"))
      (node (ref "R7") (pin "2") (pinfunction "2_2") (pintype "passive"))
    )
    (net (code "43") (name "Net-(Q5-C)") (class "Default")
      (node (ref "Q5") (pin "3") (pinfunction "C_3") (pintype "passive"))
      (node (ref "R4") (pin "1") (pinfunction "1_1") (pintype "passive"))
    )
    (net (code "44") (name "Net-(Q6-B)") (class "Default")
      (node (ref "Q6") (pin "1") (pinfunction "B_1") (pintype "passive"))
      (node (ref "R8") (pin "2") (pinfunction "2_2") (pintype "passive"))
    )
    (net (code "45") (name "Net-(Q6-C)") (class "Default")
      (node (ref "Q6") (pin "3") (pinfunction "C_3") (pintype "passive"))
      (node (ref "R5") (pin "1") (pinfunction "1_1") (pintype "passive"))
    )
    (net (code "46") (name "Net-(Q8-B)") (class "Default")
      (node (ref "Q8") (pin "1") (pinfunction "B_1") (pintype "passive"))
      (node (ref "Q9") (pin "2") (pinfunction "E_2") (pintype "passive"))
    )
    (net (code "47") (name "Net-(Q8-C)") (class "Default")
      (node (ref "D1") (pin "A") (pinfunction "A_A") (pintype "passive"))
      (node (ref "Q8") (pin "3") (pinfunction "C_3") (pintype "passive"))
      (node (ref "R12") (pin "1") (pinfunction "1_1") (pintype "passive"))
      (node (ref "SP1") (pin "1") (pinfunction "+_1") (pintype "passive"))
    )
    (net (code "48") (name "Net-(Q9-B)") (class "Default")
      (node (ref "Q9") (pin "1") (pinfunction "B_1") (pintype "passive"))
      (node (ref "R28") (pin "2") (pinfunction "2_2") (pintype "passive"))
    )
    (net (code "49") (name "Net-(Q9-C)") (class "Default")
      (node (ref "Q9") (pin "3") (pinfunction "C_3") (pintype "passive"))
      (node (ref "R27") (pin "1") (pinfunction "1_1") (pintype "passive"))
    )
    (net (code "50") (name "Net-(Q10-B)") (class "Default")
      (node (ref "B1") (pin "-") (pinfunction "-_-") (pintype "passive"))
      (node (ref "D5") (pin "C") (pinfunction "C_C") (pintype "passive"))
      (node (ref "Q10") (pin "1") (pinfunction "B_1") (pintype "passive"))
      (node (ref "R22") (pin "1") (pinfunction "1_1") (pintype "passive"))
    )
    (net (code "51") (name "Net-(Q10-C)") (class "Default")
      (node (ref "OK1") (pin "2") (pinfunction "2_2") (pintype "passive"))
      (node (ref "Q10") (pin "3") (pinfunction "C_3") (pintype "passive"))
    )
    (net (code "52") (name "Net-(Q10-E)") (class "Default")
      (node (ref "C6") (pin "2") (pinfunction "2_2") (pintype "passive"))
      (node (ref "D5") (pin "A") (pinfunction "A_A") (pintype "passive"))
      (node (ref "Q10") (pin "2") (pinfunction "E_2") (pintype "passive"))
    )
    (net (code "53") (name "Net-(Q11A-D)") (class "Default")
      (node (ref "J9") (pin "3") (pinfunction "3_3") (pintype "bidirectional"))
      (node (ref "Q11") (pin "D2") (pinfunction "D_D2") (pintype "bidirectional"))
    )
    (net (code "54") (name "Net-(Q11A-G)") (class "Default")
      (node (ref "Q11") (pin "G2") (pinfunction "G_G2") (pintype "bidirectional"))
      (node (ref "Q12") (pin "3") (pinfunction "C_3") (pintype "passive"))
      (node (ref "R32") (pin "1") (pinfunction "1_1") (pintype "passive"))
    )
    (net (code "55") (name "Net-(Q11B-D)") (class "Default")
      (node (ref "J9") (pin "2") (pinfunction "2_2") (pintype "bidirectional"))
      (node (ref "Q11") (pin "D1") (pinfunction "D_D1") (pintype "bidirectional"))
    )
    (net (code "56") (name "Net-(Q11B-G)") (class "Default")
      (node (ref "Q11") (pin "G1") (pinfunction "G_G1") (pintype "bidirectional"))
      (node (ref "Q12") (pin "6") (pinfunction "C_6") (pintype "passive"))
      (node (ref "R31") (pin "1") (pinfunction "1_1") (pintype "passive"))
    )
    (net (code "57") (name "Net-(Q12A-B)") (class "Default")
      (node (ref "Q12") (pin "5") (pinfunction "B_5") (pintype "passive"))
      (node (ref "R34") (pin "1") (pinfunction "1_1") (pintype "passive"))
    )
    (net (code "58") (name "Net-(Q12B-B)") (class "Default")
      (node (ref "Q12") (pin "2") (pinfunction "B_2") (pintype "passive"))
      (node (ref "R33") (pin "1") (pinfunction "1_1") (pintype "passive"))
    )
    (net (code "59") (name "Net-(TR1-A1)") (class "Default")
      (node (ref "J17") (pin "A1") (pinfunction "1_A1") (pintype "passive"))
      (node (ref "J17") (pin "A2") (pinfunction "1_A2") (pintype "passive"))
      (node (ref "R13") (pin "2") (pinfunction "2_2") (pintype "passive"))
      (node (ref "TR1") (pin "1") (pinfunction "A1_1") (pintype "passive"))
    )
    (net (code "60") (name "Net-(TR1-G)") (class "Default")
      (node (ref "R2") (pin "2") (pinfunction "2_2") (pintype "passive"))
      (node (ref "TR1") (pin "3") (pinfunction "G_3") (pintype "passive"))
    )
    (net (code "61") (name "Net-(U2-T+)") (class "Default")
      (node (ref "C3") (pin "2") (pinfunction "2_2") (pintype "passive"))
      (node (ref "FB1") (pin "2") (pinfunction "2_2") (pintype "passive"))
      (node (ref "U2") (pin "3") (pinfunction "T+_3") (pintype "bidirectional"))
    )
    (net (code "62") (name "Net-(U2-T-)") (class "Default")
      (node (ref "C3") (pin "1") (pinfunction "1_1") (pintype "passive"))
      (node (ref "FB2") (pin "2") (pinfunction "2_2") (pintype "passive"))
      (node (ref "U2") (pin "2") (pinfunction "T-_2") (pintype "bidirectional"))
    )
    (net (code "63") (name "Net-(U4-AIN0)") (class "Default")
      (node (ref "J6") (pin "3") (pinfunction "3_3") (pintype "bidirectional"))
      (node (ref "U4") (pin "4") (pinfunction "AIN0_4") (pintype "bidirectional"))
    )
    (net (code "64") (name "Net-(U4-SCL)") (class "Default")
      (node (ref "U4") (pin "10") (pinfunction "SCL_10") (pintype "bidirectional"))
      (node (ref "U5") (pin "P$8") (pinfunction "B1_P$8") (pintype "bidirectional"))
    )
    (net (code "65") (name "Net-(U4-SDA)") (class "Default")
      (node (ref "U4") (pin "9") (pinfunction "SDA_9") (pintype "bidirectional"))
      (node (ref "U5") (pin "P$1") (pinfunction "B2_P$1") (pintype "bidirectional"))
    )
    (net (code "66") (name "PA0") (class "Default")
      (node (ref "OK1") (pin "4") (pinfunction "4_4") (pintype "passive"))
      (node (ref "R14") (pin "1") (pinfunction "1_1") (pintype "passive"))
      (node (ref "U1") (pin "P2$15") (pinfunction "PA0_P2$15") (pintype "bidirectional"))
    )
    (net (code "67") (name "PA1") (class "Default")
      (node (ref "R1") (pin "1") (pinfunction "1_1") (pintype "passive"))
      (node (ref "U1") (pin "P2$14") (pinfunction "PA1_P2$14") (pintype "bidirectional"))
    )
    (net (code "68") (name "PA6") (class "Default")
      (node (ref "U1") (pin "P2$9") (pinfunction "PA6_P2$9") (pintype "bidirectional"))
      (node (ref "U2") (pin "6") (pinfunction "~{CS}_6") (pintype "bidirectional"))
    )
    (net (code "69") (name "PA8") (class "Default")
      (node (ref "R34") (pin "2") (pinfunction "2_2") (pintype "passive"))
      (node (ref "R36") (pin "2") (pinfunction "2_2") (pintype "passive"))
      (node (ref "U1") (pin "P1$5") (pinfunction "PA8_P1$5") (pintype "bidirectional"))
    )
    (net (code "70") (name "PA15") (class "Default")
      (node (ref "R33") (pin "2") (pinfunction "2_2") (pintype "passive"))
      (node (ref "R37") (pin "2") (pinfunction "2_2") (pintype "passive"))
      (node (ref "U1") (pin "P1$10") (pinfunction "PA15_P1$10") (pintype "bidirectional"))
    )
    (net (code "71") (name "PB0") (class "Default")
      (node (ref "J8") (pin "2") (pinfunction "2_2") (pintype "bidirectional"))
      (node (ref "R16") (pin "2") (pinfunction "2_2") (pintype "passive"))
      (node (ref "U1") (pin "P2$7") (pinfunction "PB0_P2$7") (pintype "bidirectional"))
    )
    (net (code "72") (name "PB1") (class "Default")
      (node (ref "U1") (pin "P2$6") (pinfunction "PB1_P2$6") (pintype "bidirectional"))
    )
    (net (code "73") (name "PB5") (class "Default")
      (node (ref "U1") (pin "P1$13") (pinfunction "PB5_P1$13") (pintype "bidirectional"))
    )
    (net (code "74") (name "PB8") (class "Default")
      (node (ref "J8") (pin "1") (pinfunction "1_1") (pintype "bidirectional"))
      (node (ref "U1") (pin "P1$16") (pinfunction "PB8_P1$16") (pintype "bidirectional"))
    )
    (net (code "75") (name "PB9") (class "Default")
      (node (ref "J8") (pin "5") (pinfunction "5_5") (pintype "bidirectional"))
      (node (ref "U1") (pin "P1$17") (pinfunction "PB9_P1$17") (pintype "bidirectional"))
    )
    (net (code "76") (name "PB12") (class "Default")
      (node (ref "R40") (pin "2") (pinfunction "2_2") (pintype "passive"))
      (node (ref "R6") (pin "1") (pinfunction "1_1") (pintype "passive"))
      (node (ref "U1") (pin "P1$1") (pinfunction "PB12_P1$1") (pintype "bidirectional"))
    )
    (net (code "77") (name "PB13") (class "Default")
      (node (ref "R39") (pin "2") (pinfunction "2_2") (pintype "passive"))
      (node (ref "R7") (pin "1") (pinfunction "1_1") (pintype "passive"))
      (node (ref "U1") (pin "P1$2") (pinfunction "PB13_P1$2") (pintype "bidirectional"))
    )
    (net (code "78") (name "PB14") (class "Default")
      (node (ref "R28") (pin "1") (pinfunction "1_1") (pintype "passive"))
      (node (ref "R41") (pin "2") (pinfunction "2_2") (pintype "passive"))
      (node (ref "U1") (pin "P1$3") (pinfunction "PB14_P1$3") (pintype "bidirectional"))
    )
    (net (code "79") (name "PB15") (class "Default")
      (node (ref "J5") (pin "2") (pinfunction "2_2") (pintype "bidirectional"))
      (node (ref "U1") (pin "P1$4") (pinfunction "PB15_P1$4") (pintype "bidirectional"))
    )
    (net (code "80") (name "PC13") (class "Default")
      (node (ref "R38") (pin "2") (pinfunction "2_2") (pintype "passive"))
      (node (ref "R8") (pin "1") (pinfunction "1_1") (pintype "passive"))
      (node (ref "U1") (pin "P2$19") (pinfunction "PC13_P2$19") (pintype "bidirectional"))
    )
    (net (code "81") (name "PC14") (class "Default")
      (node (ref "C14") (pin "1") (pinfunction "1_1") (pintype "passive"))
      (node (ref "R19") (pin "2") (pinfunction "2_2") (pintype "passive"))
      (node (ref "U1") (pin "P2$18") (pinfunction "PC14_P2$18") (pintype "bidirectional"))
    )
    (net (code "82") (name "PC15") (class "Default")
      (node (ref "C4") (pin "1") (pinfunction "1_1") (pintype "passive"))
      (node (ref "R29") (pin "2") (pinfunction "2_2") (pintype "passive"))
      (node (ref "U1") (pin "P2$17") (pinfunction "PC15_P2$17") (pintype "bidirectional"))
    )
    (net (code "83") (name "SPI1_MISO") (class "Default")
      (node (ref "U1") (pin "P1$12") (pinfunction "PB4_P1$12") (pintype "bidirectional"))
      (node (ref "U2") (pin "7") (pinfunction "(MI)SO_7") (pintype "bidirectional"))
    )
    (net (code "84") (name "SPI1_MOSI") (class "Default")
      (node (ref "U1") (pin "P2$8") (pinfunction "PA7_P2$8") (pintype "bidirectional"))
    )
    (net (code "85") (name "SPI1_NSS") (class "Default")
      (node (ref "U1") (pin "P2$11") (pinfunction "PA4_P2$11") (pintype "bidirectional"))
    )
    (net (code "86") (name "SPI1_SCK") (class "Default")
      (node (ref "U1") (pin "P2$10") (pinfunction "PA5_P2$10") (pintype "bidirectional"))
      (node (ref "U2") (pin "5") (pinfunction "SCK_5") (pintype "bidirectional"))
    )
    (net (code "87") (name "UART1_RX") (class "Default")
      (node (ref "J27") (pin "2") (pinfunction "2_2") (pintype "passive"))
      (node (ref "U1") (pin "P1$7") (pinfunction "PA10_P1$7") (pintype "bidirectional"))
    )
    (net (code "88") (name "UART1_TX") (class "Default")
      (node (ref "J27") (pin "3") (pinfunction "3_3") (pintype "passive"))
      (node (ref "U1") (pin "P1$6") (pinfunction "PA9_P1$6") (pintype "bidirectional"))
    )
    (net (code "89") (name "UART2_RX") (class "Default")
      (node (ref "J1") (pin "2") (pinfunction "2_2") (pintype "bidirectional"))
      (node (ref "U1") (pin "P2$12") (pinfunction "PA3_P2$12") (pintype "bidirectional"))
    )
    (net (code "90") (name "UART2_TX") (class "Default")
      (node (ref "J1") (pin "3") (pinfunction "3_3") (pintype "bidirectional"))
      (node (ref "U1") (pin "P2$13") (pinfunction "PA2_P2$13") (pintype "bidirectional"))
    )
    (net (code "91") (name "unconnected-(K3-DS2-Pad5)") (class "Default")
      (node (ref "K3") (pin "5") (pinfunction "DS2_5") (pintype "passive"))
    )
    (net (code "92") (name "unconnected-(U1-PA11-PadP1$8)") (class "Default")
      (node (ref "U1") (pin "P1$8") (pinfunction "PA11_P1$8") (pintype "bidirectional"))
    )
    (net (code "93") (name "unconnected-(U1-PA12-PadP1$9)") (class "Default")
      (node (ref "U1") (pin "P1$9") (pinfunction "PA12_P1$9") (pintype "bidirectional"))
    )
    (net (code "94") (name "unconnected-(U1-VB-PadP2$20)") (class "Default")
      (node (ref "U1") (pin "P2$20") (pinfunction "VB_P2$20") (pintype "bidirectional"))
    )
    (net (code "95") (name "unconnected-(U4-ALERT-Pad2)") (class "Default")
      (node (ref "U4") (pin "2") (pinfunction "ALERT_2") (pintype "bidirectional"))
    )
  )
)
